# Sheet1.net
KiCad netlist of a schematic drawn in Altium Designer
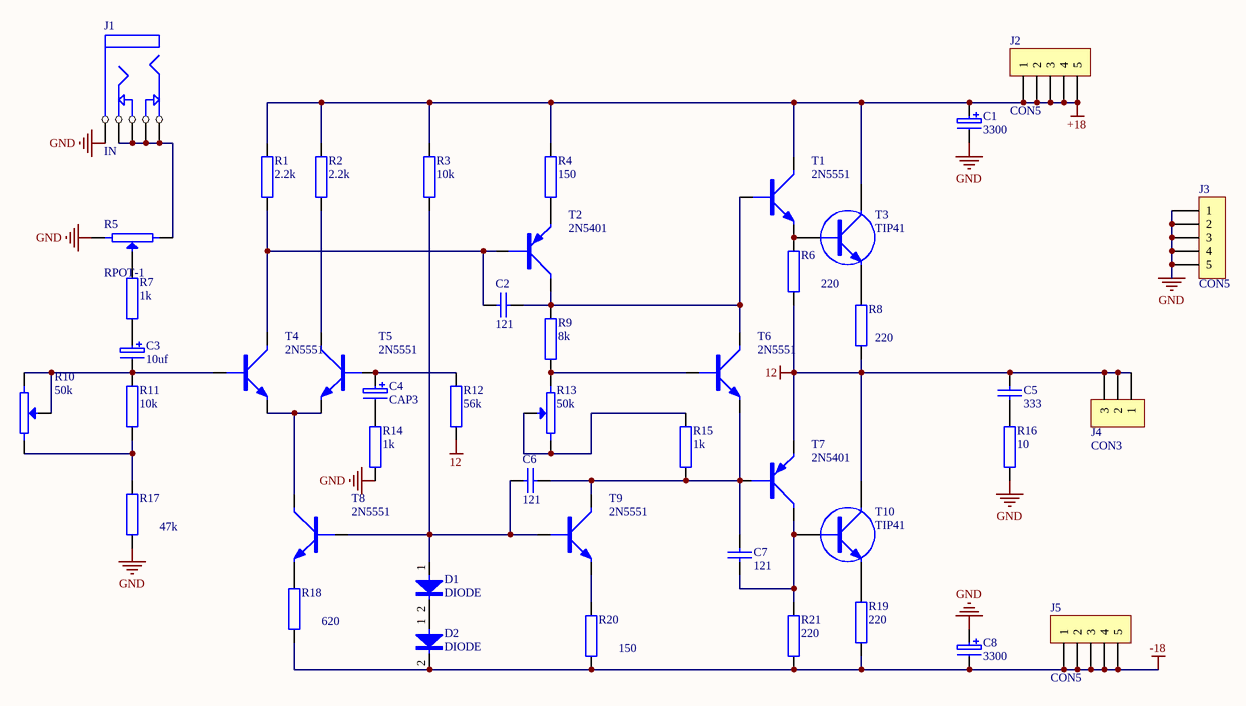
[diagram p0: Sheet1.SchDoc]

(export (version "E")
  (design (tool "Eeschema 10.0.6"))
  (components
    (comp (ref "C1") (value "3300") (footprint "C18") (libsource (lib "C电容") (part "CAP3")))
    (comp (ref "C2") (value "121") (footprint "CAP2") (libsource (lib "C电容") (part "CAP1")))
    (comp (ref "C3") (value "10uf") (footprint "CAO2") (libsource (lib "C电容") (part "CAP3")))
    (comp (ref "C4") (value "CAP3") (footprint "CAO2") (libsource (lib "C电容") (part "CAP3")))
    (comp (ref "C5") (value "333") (footprint "CAP2") (libsource (lib "C电容") (part "CAP1")))
    (comp (ref "C6") (value "121") (footprint "CAP2") (libsource (lib "C电容") (part "CAP1")))
    (comp (ref "C7") (value "121") (footprint "CAP2") (libsource (lib "C电容") (part "CAP1")))
    (comp (ref "C8") (value "3300") (footprint "C18") (libsource (lib "C电容") (part "CAP3")))
    (comp (ref "D1") (value "DIODE") (footprint "DIODE0.2") (libsource (lib "DEODE") (part "DIODE")))
    (comp (ref "D2") (value "DIODE") (footprint "DIODE0.2") (libsource (lib "DEODE") (part "DIODE")))
    (comp (ref "J1") (value "IN") (footprint "SOUND1") (libsource (lib "接口") (part "PHONEJACK STEREO SW")))
    (comp (ref "J2")
      (value "CON5")
      (footprint "sip-5")
      (description "Connector")
      (libsource (lib "") (part "CON5_1"))
    )
    (comp (ref "J3")
      (value "CON5")
      (footprint "sip-5")
      (description "Connector")
      (libsource (lib "接口") (part "CON5"))
    )
    (comp (ref "J4")
      (value "CON3")
      (footprint "sip-3")
      (description "Connector")
      (libsource (lib "接口") (part "CON3"))
    )
    (comp (ref "J5")
      (value "CON5")
      (footprint "sip-5")
      (description "Connector")
      (libsource (lib "") (part "CON5_1"))
    )
    (comp (ref "R1") (value "2.2k") (footprint "AXIAL0.3") (libsource (lib "R电阻") (part "RES")))
    (comp (ref "R2") (value "2.2k") (footprint "AXIAL0.3") (libsource (lib "R电阻") (part "RES")))
    (comp (ref "R3") (value "10k") (footprint "AXIAL0.3") (libsource (lib "R电阻") (part "RES")))
    (comp (ref "R4") (value "150") (footprint "AXIAL0.3") (libsource (lib "R电阻") (part "RES")))
    (comp (ref "R5")
      (value "RPOT-1")
      (footprint "RVR-A")
      (description "Potentiometer")
      (libsource (lib "R电阻") (part "RPOT-1"))
    )
    (comp (ref "R6") (value "220") (footprint "AXIAL0.3") (libsource (lib "R电阻") (part "RES")))
    (comp (ref "R7") (value "1k") (footprint "AXIAL0.3") (libsource (lib "R电阻") (part "RES")))
    (comp (ref "R8") (value "220") (footprint "AXIAL1.0") (libsource (lib "R电阻") (part "RES")))
    (comp (ref "R9") (value "8k") (footprint "AXIAL0.3") (libsource (lib "R电阻") (part "RES")))
    (comp (ref "R10")
      (value "50k")
      (footprint "RVR-4")
      (description "Potentiometer")
      (libsource (lib "R电阻") (part "RPOT-1"))
    )
    (comp (ref "R11") (value "10k") (footprint "AXIAL0.3") (libsource (lib "R电阻") (part "RES")))
    (comp (ref "R12") (value "56k") (footprint "AXIAL0.3") (libsource (lib "R电阻") (part "RES")))
    (comp (ref "R13")
      (value "50k")
      (footprint "RVR-4")
      (description "Potentiometer")
      (libsource (lib "R电阻") (part "RPOT-1"))
    )
    (comp (ref "R14") (value "1k") (footprint "AXIAL0.3") (libsource (lib "R电阻") (part "RES")))
    (comp (ref "R15") (value "1k") (footprint "AXIAL0.3") (libsource (lib "R电阻") (part "RES")))
    (comp (ref "R16") (value "10") (footprint "AXIAL0.3") (libsource (lib "R电阻") (part "RES")))
    (comp (ref "R17") (value "47k") (footprint "AXIAL0.3") (libsource (lib "R电阻") (part "RES")))
    (comp (ref "R18") (value "620") (footprint "AXIAL0.3") (libsource (lib "R电阻") (part "RES")))
    (comp (ref "R19") (value "220") (footprint "AXIAL1.0") (libsource (lib "R电阻") (part "RES")))
    (comp (ref "R20") (value "150") (footprint "AXIAL0.3") (libsource (lib "R电阻") (part "RES")))
    (comp (ref "R21") (value "220") (footprint "AXIAL0.3") (libsource (lib "R电阻") (part "RES")))
    (comp (ref "T1")
      (value "2N5551")
      (footprint "TO-92")
      (description "NPN,小功率")
      (libsource (lib "V三极管") (part "2N5551"))
    )
    (comp (ref "T2")
      (value "2N5401")
      (footprint "TO-92")
      (description "PNP,小功率")
      (libsource (lib "V三极管") (part "2N5401"))
    )
    (comp (ref "T3")
      (value "TIP41")
      (footprint "TO-220")
      (description "NPN PLASTIC POWER TRANSISTORS")
      (libsource (lib "V三极管") (part "TIP41"))
    )
    (comp (ref "T4")
      (value "2N5551")
      (footprint "TO-92")
      (description "NPN,小功率")
      (libsource (lib "V三极管") (part "2N5551"))
    )
    (comp (ref "T5")
      (value "2N5551")
      (footprint "TO-92")
      (description "NPN,小功率")
      (libsource (lib "V三极管") (part "2N5551"))
    )
    (comp (ref "T6")
      (value "2N5551")
      (footprint "TO-92")
      (description "NPN,小功率")
      (libsource (lib "V三极管") (part "2N5551"))
    )
    (comp (ref "T7")
      (value "2N5401")
      (footprint "TO-92")
      (description "PNP,小功率")
      (libsource (lib "V三极管") (part "2N5401"))
    )
    (comp (ref "T8")
      (value "2N5551")
      (footprint "TO-92")
      (description "NPN,小功率")
      (libsource (lib "V三极管") (part "2N5551"))
    )
    (comp (ref "T9")
      (value "2N5551")
      (footprint "TO-92")
      (description "NPN,小功率")
      (libsource (lib "V三极管") (part "2N5551"))
    )
    (comp (ref "T10")
      (value "TIP41")
      (footprint "TO-220")
      (description "NPN PLASTIC POWER TRANSISTORS")
      (libsource (lib "V三极管") (part "TIP41"))
    )
  )
  (nets
    (net (code "1") (name "+18") (class "Default")
      (node (ref "C1") (pin "1") (pintype "passive"))
      (node (ref "J2") (pin "1") (pinfunction "1_1") (pintype "passive"))
      (node (ref "J2") (pin "2") (pinfunction "2_2") (pintype "passive"))
      (node (ref "J2") (pin "3") (pinfunction "3_3") (pintype "passive"))
      (node (ref "J2") (pin "4") (pinfunction "4_4") (pintype "passive"))
      (node (ref "J2") (pin "5") (pinfunction "5_5") (pintype "passive"))
      (node (ref "R1") (pin "2") (pinfunction "2_2") (pintype "passive"))
      (node (ref "R2") (pin "2") (pinfunction "2_2") (pintype "passive"))
      (node (ref "R3") (pin "2") (pinfunction "2_2") (pintype "passive"))
      (node (ref "R4") (pin "2") (pinfunction "2_2") (pintype "passive"))
      (node (ref "T1") (pin "3") (pinfunction "C_3") (pintype "passive"))
      (node (ref "T3") (pin "2") (pinfunction "C_2") (pintype "passive"))
    )
    (net (code "2") (name "-18") (class "Default")
      (node (ref "C8") (pin "2") (pintype "passive"))
      (node (ref "D2") (pin "2") (pinfunction "2_2") (pintype "passive"))
      (node (ref "J5") (pin "1") (pinfunction "1_1") (pintype "passive"))
      (node (ref "J5") (pin "2") (pinfunction "2_2") (pintype "passive"))
      (node (ref "J5") (pin "3") (pinfunction "3_3") (pintype "passive"))
      (node (ref "J5") (pin "4") (pinfunction "4_4") (pintype "passive"))
      (node (ref "J5") (pin "5") (pinfunction "5_5") (pintype "passive"))
      (node (ref "R18") (pin "1") (pinfunction "1_1") (pintype "passive"))
      (node (ref "R19") (pin "1") (pinfunction "1_1") (pintype "passive"))
      (node (ref "R20") (pin "1") (pinfunction "1_1") (pintype "passive"))
      (node (ref "R21") (pin "2") (pinfunction "2_2") (pintype "passive"))
    )
    (net (code "3") (name "12") (class "Default")
      (node (ref "C5") (pin "1") (pinfunction "1_1") (pintype "passive"))
      (node (ref "J4") (pin "1") (pinfunction "1_1") (pintype "passive"))
      (node (ref "J4") (pin "2") (pinfunction "2_2") (pintype "passive"))
      (node (ref "J4") (pin "3") (pinfunction "3_3") (pintype "passive"))
      (node (ref "R12") (pin "2") (pinfunction "2_2") (pintype "passive"))
      (node (ref "R6") (pin "1") (pinfunction "1_1") (pintype "passive"))
      (node (ref "R8") (pin "1") (pinfunction "1_1") (pintype "passive"))
      (node (ref "T10") (pin "2") (pinfunction "C_2") (pintype "passive"))
      (node (ref "T7") (pin "1") (pinfunction "e_1") (pintype "passive"))
    )
    (net (code "4") (name "GND") (class "Default")
      (node (ref "C1") (pin "2") (pintype "passive"))
      (node (ref "C8") (pin "1") (pintype "passive"))
      (node (ref "J1") (pin "5") (pinfunction "E_5") (pintype "passive"))
      (node (ref "J3") (pin "1") (pinfunction "1_1") (pintype "passive"))
      (node (ref "J3") (pin "2") (pinfunction "2_2") (pintype "passive"))
      (node (ref "J3") (pin "3") (pinfunction "3_3") (pintype "passive"))
      (node (ref "J3") (pin "4") (pinfunction "4_4") (pintype "passive"))
      (node (ref "J3") (pin "5") (pinfunction "5_5") (pintype "passive"))
      (node (ref "R14") (pin "1") (pinfunction "1_1") (pintype "passive"))
      (node (ref "R16") (pin "1") (pinfunction "1_1") (pintype "passive"))
      (node (ref "R17") (pin "1") (pinfunction "1_1") (pintype "passive"))
      (node (ref "R5") (pin "3") (pinfunction "3_3") (pintype "passive"))
    )
    (net (code "5") (name "Net-(C3-Pad1)") (class "Default")
      (node (ref "C3") (pin "1") (pintype "passive"))
      (node (ref "R7") (pin "1") (pinfunction "1_1") (pintype "passive"))
    )
    (net (code "6") (name "Net-(C4-Pad2)") (class "Default")
      (node (ref "C4") (pin "2") (pintype "passive"))
      (node (ref "R14") (pin "2") (pinfunction "2_2") (pintype "passive"))
    )
    (net (code "7") (name "Net-(C5-Pad2)") (class "Default")
      (node (ref "C5") (pin "2") (pinfunction "2_2") (pintype "passive"))
      (node (ref "R16") (pin "2") (pinfunction "2_2") (pintype "passive"))
    )
    (net (code "8") (name "Net-(D1-Pad2)") (class "Default")
      (node (ref "D1") (pin "2") (pinfunction "2_2") (pintype "passive"))
      (node (ref "D2") (pin "1") (pinfunction "1_1") (pintype "passive"))
    )
    (net (code "9") (name "Net-(J1-A)") (class "Default")
      (node (ref "J1") (pin "1") (pinfunction "A_1") (pintype "passive"))
      (node (ref "J1") (pin "2") (pinfunction "B_2") (pintype "passive"))
      (node (ref "J1") (pin "3") (pinfunction "C_3") (pintype "passive"))
      (node (ref "J1") (pin "4") (pinfunction "D_4") (pintype "passive"))
      (node (ref "R5") (pin "1") (pinfunction "1_1") (pintype "passive"))
    )
    (net (code "10") (name "Net-(R5-W)") (class "Default")
      (node (ref "R5") (pin "2") (pinfunction "W_2") (pintype "passive"))
      (node (ref "R7") (pin "2") (pinfunction "2_2") (pintype "passive"))
    )
    (net (code "11") (name "Net-(R10-Pad3)") (class "Default")
      (node (ref "R10") (pin "3") (pinfunction "3_3") (pintype "passive"))
      (node (ref "R11") (pin "1") (pinfunction "1_1") (pintype "passive"))
      (node (ref "R17") (pin "2") (pinfunction "2_2") (pintype "passive"))
    )
    (net (code "12") (name "Net-(R10-W)") (class "Default")
      (node (ref "C3") (pin "2") (pintype "passive"))
      (node (ref "R10") (pin "1") (pinfunction "1_1") (pintype "passive"))
      (node (ref "R10") (pin "2") (pinfunction "W_2") (pintype "passive"))
      (node (ref "R11") (pin "2") (pinfunction "2_2") (pintype "passive"))
      (node (ref "T4") (pin "2") (pinfunction "B_2") (pintype "passive"))
    )
    (net (code "13") (name "Net-(R13-W)") (class "Default")
      (node (ref "R13") (pin "1") (pinfunction "1_1") (pintype "passive"))
      (node (ref "R13") (pin "2") (pinfunction "W_2") (pintype "passive"))
      (node (ref "R15") (pin "2") (pinfunction "2_2") (pintype "passive"))
    )
    (net (code "14") (name "Net-(T1-B)") (class "Default")
      (node (ref "C2") (pin "1") (pinfunction "1_1") (pintype "passive"))
      (node (ref "R9") (pin "2") (pinfunction "2_2") (pintype "passive"))
      (node (ref "T1") (pin "2") (pinfunction "B_2") (pintype "passive"))
      (node (ref "T2") (pin "3") (pinfunction "c_3") (pintype "passive"))
      (node (ref "T6") (pin "3") (pinfunction "C_3") (pintype "passive"))
    )
    (net (code "15") (name "Net-(T1-E)") (class "Default")
      (node (ref "R6") (pin "2") (pinfunction "2_2") (pintype "passive"))
      (node (ref "T1") (pin "1") (pinfunction "E_1") (pintype "passive"))
      (node (ref "T3") (pin "1") (pinfunction "B_1") (pintype "passive"))
    )
    (net (code "16") (name "Net-(T2-B)") (class "Default")
      (node (ref "C2") (pin "2") (pinfunction "2_2") (pintype "passive"))
      (node (ref "R1") (pin "1") (pinfunction "1_1") (pintype "passive"))
      (node (ref "T2") (pin "2") (pinfunction "B_2") (pintype "passive"))
      (node (ref "T4") (pin "3") (pinfunction "C_3") (pintype "passive"))
    )
    (net (code "17") (name "Net-(T2-e)") (class "Default")
      (node (ref "R4") (pin "1") (pinfunction "1_1") (pintype "passive"))
      (node (ref "T2") (pin "1") (pinfunction "e_1") (pintype "passive"))
    )
    (net (code "18") (name "Net-(T3-E)") (class "Default")
      (node (ref "R8") (pin "2") (pinfunction "2_2") (pintype "passive"))
      (node (ref "T3") (pin "3") (pinfunction "E_3") (pintype "passive"))
    )
    (net (code "19") (name "Net-(T4-E)") (class "Default")
      (node (ref "T4") (pin "1") (pinfunction "E_1") (pintype "passive"))
      (node (ref "T5") (pin "1") (pinfunction "E_1") (pintype "passive"))
      (node (ref "T8") (pin "3") (pinfunction "C_3") (pintype "passive"))
    )
    (net (code "20") (name "Net-(T5-B)") (class "Default")
      (node (ref "C4") (pin "1") (pintype "passive"))
      (node (ref "R12") (pin "1") (pinfunction "1_1") (pintype "passive"))
      (node (ref "T5") (pin "2") (pinfunction "B_2") (pintype "passive"))
    )
    (net (code "21") (name "Net-(T5-C)") (class "Default")
      (node (ref "R2") (pin "1") (pinfunction "1_1") (pintype "passive"))
      (node (ref "T5") (pin "3") (pinfunction "C_3") (pintype "passive"))
    )
    (net (code "22") (name "Net-(T6-B)") (class "Default")
      (node (ref "R13") (pin "3") (pinfunction "3_3") (pintype "passive"))
      (node (ref "R9") (pin "1") (pinfunction "1_1") (pintype "passive"))
      (node (ref "T6") (pin "2") (pinfunction "B_2") (pintype "passive"))
    )
    (net (code "23") (name "Net-(T6-E)") (class "Default")
      (node (ref "C6") (pin "1") (pinfunction "1_1") (pintype "passive"))
      (node (ref "C7") (pin "1") (pinfunction "1_1") (pintype "passive"))
      (node (ref "R15") (pin "1") (pinfunction "1_1") (pintype "passive"))
      (node (ref "T6") (pin "1") (pinfunction "E_1") (pintype "passive"))
      (node (ref "T7") (pin "2") (pinfunction "B_2") (pintype "passive"))
      (node (ref "T9") (pin "3") (pinfunction "C_3") (pintype "passive"))
    )
    (net (code "24") (name "Net-(T8-B)") (class "Default")
      (node (ref "C6") (pin "2") (pinfunction "2_2") (pintype "passive"))
      (node (ref "D1") (pin "1") (pinfunction "1_1") (pintype "passive"))
      (node (ref "R3") (pin "1") (pinfunction "1_1") (pintype "passive"))
      (node (ref "T8") (pin "2") (pinfunction "B_2") (pintype "passive"))
      (node (ref "T9") (pin "2") (pinfunction "B_2") (pintype "passive"))
    )
    (net (code "25") (name "Net-(T8-E)") (class "Default")
      (node (ref "R18") (pin "2") (pinfunction "2_2") (pintype "passive"))
      (node (ref "T8") (pin "1") (pinfunction "E_1") (pintype "passive"))
    )
    (net (code "26") (name "Net-(T9-E)") (class "Default")
      (node (ref "R20") (pin "2") (pinfunction "2_2") (pintype "passive"))
      (node (ref "T9") (pin "1") (pinfunction "E_1") (pintype "passive"))
    )
    (net (code "27") (name "Net-(T10-B)") (class "Default")
      (node (ref "C7") (pin "2") (pinfunction "2_2") (pintype "passive"))
      (node (ref "R21") (pin "1") (pinfunction "1_1") (pintype "passive"))
      (node (ref "T10") (pin "1") (pinfunction "B_1") (pintype "passive"))
      (node (ref "T7") (pin "3") (pinfunction "c_3") (pintype "passive"))
    )
    (net (code "28") (name "Net-(T10-E)") (class "Default")
      (node (ref "R19") (pin "2") (pinfunction "2_2") (pintype "passive"))
      (node (ref "T10") (pin "3") (pinfunction "E_3") (pintype "passive"))
    )
  )
)
